# pneuBoard.net
KiCad netlist of a schematic drawn in EAGLE
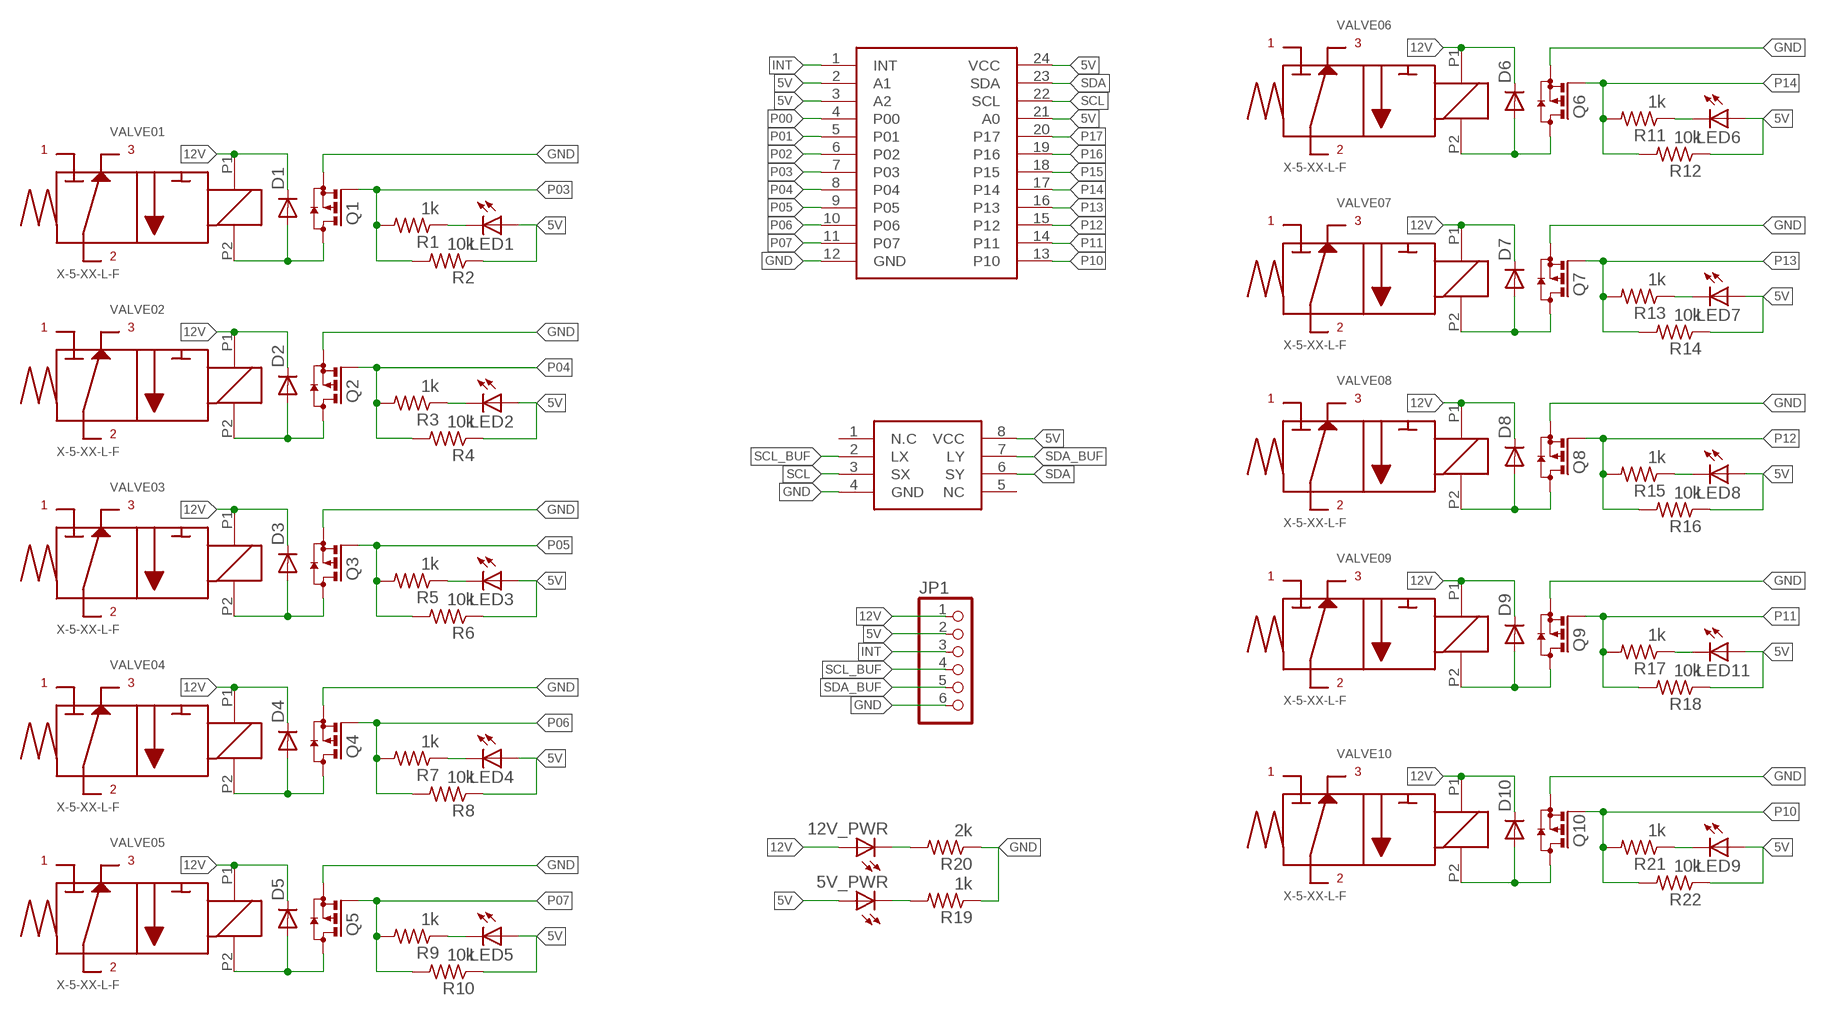
[diagram p0: schematic, sheet 1]

(export (version "E")
  (design (tool "Eeschema 10.0.6"))
  (components
    (comp (ref "5V_PWR")
      (value "LEDSML1206")
      (footprint "eagle-import:SML1206")
      (libsource (lib "eagle-import") (part "LEDSML1206"))
    )
    (comp (ref "12V_PWR")
      (value "LEDSML1206")
      (footprint "eagle-import:SML1206")
      (libsource (lib "eagle-import") (part "LEDSML1206"))
    )
    (comp (ref "D1")
      (value "DIODE-SOD123")
      (footprint "eagle-import:SOD123")
      (libsource (lib "eagle-import") (part "DIODE-SOD123"))
    )
    (comp (ref "D2")
      (value "DIODE-SOD123")
      (footprint "eagle-import:SOD123")
      (libsource (lib "eagle-import") (part "DIODE-SOD123"))
    )
    (comp (ref "D3")
      (value "DIODE-SOD123")
      (footprint "eagle-import:SOD123")
      (libsource (lib "eagle-import") (part "DIODE-SOD123"))
    )
    (comp (ref "D4")
      (value "DIODE-SOD123")
      (footprint "eagle-import:SOD123")
      (libsource (lib "eagle-import") (part "DIODE-SOD123"))
    )
    (comp (ref "D5")
      (value "DIODE-SOD123")
      (footprint "eagle-import:SOD123")
      (libsource (lib "eagle-import") (part "DIODE-SOD123"))
    )
    (comp (ref "D6")
      (value "DIODE-SOD123")
      (footprint "eagle-import:SOD123")
      (libsource (lib "eagle-import") (part "DIODE-SOD123"))
    )
    (comp (ref "D7")
      (value "DIODE-SOD123")
      (footprint "eagle-import:SOD123")
      (libsource (lib "eagle-import") (part "DIODE-SOD123"))
    )
    (comp (ref "D8")
      (value "DIODE-SOD123")
      (footprint "eagle-import:SOD123")
      (libsource (lib "eagle-import") (part "DIODE-SOD123"))
    )
    (comp (ref "D9")
      (value "DIODE-SOD123")
      (footprint "eagle-import:SOD123")
      (libsource (lib "eagle-import") (part "DIODE-SOD123"))
    )
    (comp (ref "D10")
      (value "DIODE-SOD123")
      (footprint "eagle-import:SOD123")
      (libsource (lib "eagle-import") (part "DIODE-SOD123"))
    )
    (comp (ref "JP1")
      (value "PINHD-1X6/90")
      (footprint "eagle-import:1X06_90")
      (libsource (lib "eagle-import") (part "PINHD-1X6/90"))
    )
    (comp (ref "LED1")
      (value "LEDSML1206")
      (footprint "eagle-import:SML1206")
      (libsource (lib "eagle-import") (part "LEDSML1206"))
    )
    (comp (ref "LED2")
      (value "LEDSML1206")
      (footprint "eagle-import:SML1206")
      (libsource (lib "eagle-import") (part "LEDSML1206"))
    )
    (comp (ref "LED3")
      (value "LEDSML1206")
      (footprint "eagle-import:SML1206")
      (libsource (lib "eagle-import") (part "LEDSML1206"))
    )
    (comp (ref "LED4")
      (value "LEDSML1206")
      (footprint "eagle-import:SML1206")
      (libsource (lib "eagle-import") (part "LEDSML1206"))
    )
    (comp (ref "LED5")
      (value "LEDSML1206")
      (footprint "eagle-import:SML1206")
      (libsource (lib "eagle-import") (part "LEDSML1206"))
    )
    (comp (ref "LED6")
      (value "LEDSML1206")
      (footprint "eagle-import:SML1206")
      (libsource (lib "eagle-import") (part "LEDSML1206"))
    )
    (comp (ref "LED7")
      (value "LEDSML1206")
      (footprint "eagle-import:SML1206")
      (libsource (lib "eagle-import") (part "LEDSML1206"))
    )
    (comp (ref "LED8")
      (value "LEDSML1206")
      (footprint "eagle-import:SML1206")
      (libsource (lib "eagle-import") (part "LEDSML1206"))
    )
    (comp (ref "LED9")
      (value "LEDSML1206")
      (footprint "eagle-import:SML1206")
      (libsource (lib "eagle-import") (part "LEDSML1206"))
    )
    (comp (ref "LED11")
      (value "LEDSML1206")
      (footprint "eagle-import:SML1206")
      (libsource (lib "eagle-import") (part "LEDSML1206"))
    )
    (comp (ref "Q1")
      (value "BSS84")
      (footprint "eagle-import:SOT23")
      (libsource (lib "eagle-import") (part "BSS84"))
    )
    (comp (ref "Q2")
      (value "BSS84")
      (footprint "eagle-import:SOT23")
      (libsource (lib "eagle-import") (part "BSS84"))
    )
    (comp (ref "Q3")
      (value "BSS84")
      (footprint "eagle-import:SOT23")
      (libsource (lib "eagle-import") (part "BSS84"))
    )
    (comp (ref "Q4")
      (value "BSS84")
      (footprint "eagle-import:SOT23")
      (libsource (lib "eagle-import") (part "BSS84"))
    )
    (comp (ref "Q5")
      (value "BSS84")
      (footprint "eagle-import:SOT23")
      (libsource (lib "eagle-import") (part "BSS84"))
    )
    (comp (ref "Q6")
      (value "BSS84")
      (footprint "eagle-import:SOT23")
      (libsource (lib "eagle-import") (part "BSS84"))
    )
    (comp (ref "Q7")
      (value "BSS84")
      (footprint "eagle-import:SOT23")
      (libsource (lib "eagle-import") (part "BSS84"))
    )
    (comp (ref "Q8")
      (value "BSS84")
      (footprint "eagle-import:SOT23")
      (libsource (lib "eagle-import") (part "BSS84"))
    )
    (comp (ref "Q9")
      (value "BSS84")
      (footprint "eagle-import:SOT23")
      (libsource (lib "eagle-import") (part "BSS84"))
    )
    (comp (ref "Q10")
      (value "BSS84")
      (footprint "eagle-import:SOT23")
      (libsource (lib "eagle-import") (part "BSS84"))
    )
    (comp (ref "R1")
      (value "1k")
      (footprint "eagle-import:R0603")
      (libsource (lib "eagle-import") (part "R-US_R0603"))
    )
    (comp (ref "R2")
      (value "10k")
      (footprint "eagle-import:R0603")
      (libsource (lib "eagle-import") (part "R-US_R0603"))
    )
    (comp (ref "R3")
      (value "1k")
      (footprint "eagle-import:R0603")
      (libsource (lib "eagle-import") (part "R-US_R0603"))
    )
    (comp (ref "R4")
      (value "10k")
      (footprint "eagle-import:R0603")
      (libsource (lib "eagle-import") (part "R-US_R0603"))
    )
    (comp (ref "R5")
      (value "1k")
      (footprint "eagle-import:R0603")
      (libsource (lib "eagle-import") (part "R-US_R0603"))
    )
    (comp (ref "R6")
      (value "10k")
      (footprint "eagle-import:R0603")
      (libsource (lib "eagle-import") (part "R-US_R0603"))
    )
    (comp (ref "R7")
      (value "1k")
      (footprint "eagle-import:R0603")
      (libsource (lib "eagle-import") (part "R-US_R0603"))
    )
    (comp (ref "R8")
      (value "10k")
      (footprint "eagle-import:R0603")
      (libsource (lib "eagle-import") (part "R-US_R0603"))
    )
    (comp (ref "R9")
      (value "1k")
      (footprint "eagle-import:R0603")
      (libsource (lib "eagle-import") (part "R-US_R0603"))
    )
    (comp (ref "R10")
      (value "10k")
      (footprint "eagle-import:R0603")
      (libsource (lib "eagle-import") (part "R-US_R0603"))
    )
    (comp (ref "R11")
      (value "1k")
      (footprint "eagle-import:R0603")
      (libsource (lib "eagle-import") (part "R-US_R0603"))
    )
    (comp (ref "R12")
      (value "10k")
      (footprint "eagle-import:R0603")
      (libsource (lib "eagle-import") (part "R-US_R0603"))
    )
    (comp (ref "R13")
      (value "1k")
      (footprint "eagle-import:R0603")
      (libsource (lib "eagle-import") (part "R-US_R0603"))
    )
    (comp (ref "R14")
      (value "10k")
      (footprint "eagle-import:R0603")
      (libsource (lib "eagle-import") (part "R-US_R0603"))
    )
    (comp (ref "R15")
      (value "1k")
      (footprint "eagle-import:R0603")
      (libsource (lib "eagle-import") (part "R-US_R0603"))
    )
    (comp (ref "R16")
      (value "10k")
      (footprint "eagle-import:R0603")
      (libsource (lib "eagle-import") (part "R-US_R0603"))
    )
    (comp (ref "R17")
      (value "1k")
      (footprint "eagle-import:R0603")
      (libsource (lib "eagle-import") (part "R-US_R0603"))
    )
    (comp (ref "R18")
      (value "10k")
      (footprint "eagle-import:R0603")
      (libsource (lib "eagle-import") (part "R-US_R0603"))
    )
    (comp (ref "R19")
      (value "1k")
      (footprint "eagle-import:R0603")
      (libsource (lib "eagle-import") (part "R-US_R0603"))
    )
    (comp (ref "R20")
      (value "2k")
      (footprint "eagle-import:R0603")
      (libsource (lib "eagle-import") (part "R-US_R0603"))
    )
    (comp (ref "R21")
      (value "1k")
      (footprint "eagle-import:R0603")
      (libsource (lib "eagle-import") (part "R-US_R0603"))
    )
    (comp (ref "R22")
      (value "10k")
      (footprint "eagle-import:R0603")
      (libsource (lib "eagle-import") (part "R-US_R0603"))
    )
    (comp (ref "U$1")
      (value "PCF8575C")
      (footprint "eagle-import:PW_R-PDSO-G24")
      (libsource (lib "eagle-import") (part "PCF8575C"))
    )
    (comp (ref "U$2")
      (value "P82B715")
      (footprint "eagle-import:SO8")
      (libsource (lib "eagle-import") (part "P82B715"))
    )
    (comp (ref "VALVE01")
      (value "X-5-XX-L-F")
      (footprint "eagle-import:X-SERIES")
      (libsource (lib "eagle-import") (part "X-5-XX-L-F"))
    )
    (comp (ref "VALVE02")
      (value "X-5-XX-L-F")
      (footprint "eagle-import:X-SERIES")
      (libsource (lib "eagle-import") (part "X-5-XX-L-F"))
    )
    (comp (ref "VALVE03")
      (value "X-5-XX-L-F")
      (footprint "eagle-import:X-SERIES")
      (libsource (lib "eagle-import") (part "X-5-XX-L-F"))
    )
    (comp (ref "VALVE04")
      (value "X-5-XX-L-F")
      (footprint "eagle-import:X-SERIES")
      (libsource (lib "eagle-import") (part "X-5-XX-L-F"))
    )
    (comp (ref "VALVE05")
      (value "X-5-XX-L-F")
      (footprint "eagle-import:X-SERIES")
      (libsource (lib "eagle-import") (part "X-5-XX-L-F"))
    )
    (comp (ref "VALVE06")
      (value "X-5-XX-L-F")
      (footprint "eagle-import:X-SERIES")
      (libsource (lib "eagle-import") (part "X-5-XX-L-F"))
    )
    (comp (ref "VALVE07")
      (value "X-5-XX-L-F")
      (footprint "eagle-import:X-SERIES")
      (libsource (lib "eagle-import") (part "X-5-XX-L-F"))
    )
    (comp (ref "VALVE08")
      (value "X-5-XX-L-F")
      (footprint "eagle-import:X-SERIES")
      (libsource (lib "eagle-import") (part "X-5-XX-L-F"))
    )
    (comp (ref "VALVE09")
      (value "X-5-XX-L-F")
      (footprint "eagle-import:X-SERIES")
      (libsource (lib "eagle-import") (part "X-5-XX-L-F"))
    )
    (comp (ref "VALVE10")
      (value "X-5-XX-L-F")
      (footprint "eagle-import:X-SERIES")
      (libsource (lib "eagle-import") (part "X-5-XX-L-F"))
    )
  )
  (nets
    (net (code "1") (name "5V") (class "Default")
      (node (ref "5V_PWR") (pin "A") (pinfunction "A_A") (pintype "passive"))
      (node (ref "JP1") (pin "2") (pinfunction "2_2") (pintype "passive"))
      (node (ref "LED1") (pin "A") (pinfunction "A_A") (pintype "passive"))
      (node (ref "LED11") (pin "A") (pinfunction "A_A") (pintype "passive"))
      (node (ref "LED2") (pin "A") (pinfunction "A_A") (pintype "passive"))
      (node (ref "LED3") (pin "A") (pinfunction "A_A") (pintype "passive"))
      (node (ref "LED4") (pin "A") (pinfunction "A_A") (pintype "passive"))
      (node (ref "LED5") (pin "A") (pinfunction "A_A") (pintype "passive"))
      (node (ref "LED6") (pin "A") (pinfunction "A_A") (pintype "passive"))
      (node (ref "LED7") (pin "A") (pinfunction "A_A") (pintype "passive"))
      (node (ref "LED8") (pin "A") (pinfunction "A_A") (pintype "passive"))
      (node (ref "LED9") (pin "A") (pinfunction "A_A") (pintype "passive"))
      (node (ref "R10") (pin "1") (pinfunction "1_1") (pintype "passive"))
      (node (ref "R12") (pin "1") (pinfunction "1_1") (pintype "passive"))
      (node (ref "R14") (pin "1") (pinfunction "1_1") (pintype "passive"))
      (node (ref "R16") (pin "1") (pinfunction "1_1") (pintype "passive"))
      (node (ref "R18") (pin "1") (pinfunction "1_1") (pintype "passive"))
      (node (ref "R2") (pin "1") (pinfunction "1_1") (pintype "passive"))
      (node (ref "R22") (pin "1") (pinfunction "1_1") (pintype "passive"))
      (node (ref "R4") (pin "1") (pinfunction "1_1") (pintype "passive"))
      (node (ref "R6") (pin "1") (pinfunction "1_1") (pintype "passive"))
      (node (ref "R8") (pin "1") (pinfunction "1_1") (pintype "passive"))
      (node (ref "U$1") (pin "2") (pinfunction "A1_2") (pintype "bidirectional"))
      (node (ref "U$1") (pin "21") (pinfunction "A0_21") (pintype "bidirectional"))
      (node (ref "U$1") (pin "24") (pinfunction "VCC_24") (pintype "bidirectional"))
      (node (ref "U$1") (pin "3") (pinfunction "A2_3") (pintype "bidirectional"))
      (node (ref "U$2") (pin "8") (pinfunction "VCC_8") (pintype "bidirectional"))
    )
    (net (code "2") (name "12V") (class "Default")
      (node (ref "12V_PWR") (pin "A") (pinfunction "A_A") (pintype "passive"))
      (node (ref "D1") (pin "C") (pinfunction "C_C") (pintype "passive"))
      (node (ref "D10") (pin "C") (pinfunction "C_C") (pintype "passive"))
      (node (ref "D2") (pin "C") (pinfunction "C_C") (pintype "passive"))
      (node (ref "D3") (pin "C") (pinfunction "C_C") (pintype "passive"))
      (node (ref "D4") (pin "C") (pinfunction "C_C") (pintype "passive"))
      (node (ref "D5") (pin "C") (pinfunction "C_C") (pintype "passive"))
      (node (ref "D6") (pin "C") (pinfunction "C_C") (pintype "passive"))
      (node (ref "D7") (pin "C") (pinfunction "C_C") (pintype "passive"))
      (node (ref "D8") (pin "C") (pinfunction "C_C") (pintype "passive"))
      (node (ref "D9") (pin "C") (pinfunction "C_C") (pintype "passive"))
      (node (ref "JP1") (pin "1") (pinfunction "1_1") (pintype "passive"))
      (node (ref "VALVE01") (pin "P1") (pinfunction "1_P1") (pintype "bidirectional"))
      (node (ref "VALVE02") (pin "P1") (pinfunction "1_P1") (pintype "bidirectional"))
      (node (ref "VALVE03") (pin "P1") (pinfunction "1_P1") (pintype "bidirectional"))
      (node (ref "VALVE04") (pin "P1") (pinfunction "1_P1") (pintype "bidirectional"))
      (node (ref "VALVE05") (pin "P1") (pinfunction "1_P1") (pintype "bidirectional"))
      (node (ref "VALVE06") (pin "P1") (pinfunction "1_P1") (pintype "bidirectional"))
      (node (ref "VALVE07") (pin "P1") (pinfunction "1_P1") (pintype "bidirectional"))
      (node (ref "VALVE08") (pin "P1") (pinfunction "1_P1") (pintype "bidirectional"))
      (node (ref "VALVE09") (pin "P1") (pinfunction "1_P1") (pintype "bidirectional"))
      (node (ref "VALVE10") (pin "P1") (pinfunction "1_P1") (pintype "bidirectional"))
    )
    (net (code "3") (name "GND") (class "Default")
      (node (ref "JP1") (pin "6") (pinfunction "6_6") (pintype "passive"))
      (node (ref "Q1") (pin "2") (pinfunction "S_2") (pintype "passive"))
      (node (ref "Q10") (pin "2") (pinfunction "S_2") (pintype "passive"))
      (node (ref "Q2") (pin "2") (pinfunction "S_2") (pintype "passive"))
      (node (ref "Q3") (pin "2") (pinfunction "S_2") (pintype "passive"))
      (node (ref "Q4") (pin "2") (pinfunction "S_2") (pintype "passive"))
      (node (ref "Q5") (pin "2") (pinfunction "S_2") (pintype "passive"))
      (node (ref "Q6") (pin "2") (pinfunction "S_2") (pintype "passive"))
      (node (ref "Q7") (pin "2") (pinfunction "S_2") (pintype "passive"))
      (node (ref "Q8") (pin "2") (pinfunction "S_2") (pintype "passive"))
      (node (ref "Q9") (pin "2") (pinfunction "S_2") (pintype "passive"))
      (node (ref "R19") (pin "1") (pinfunction "1_1") (pintype "passive"))
      (node (ref "R20") (pin "1") (pinfunction "1_1") (pintype "passive"))
      (node (ref "U$1") (pin "12") (pinfunction "GND_12") (pintype "bidirectional"))
      (node (ref "U$2") (pin "4") (pinfunction "GND_4") (pintype "bidirectional"))
    )
    (net (code "4") (name "INT") (class "Default")
      (node (ref "JP1") (pin "3") (pinfunction "3_3") (pintype "passive"))
      (node (ref "U$1") (pin "1") (pinfunction "INT_1") (pintype "bidirectional"))
    )
    (net (code "5") (name "Net-(5V_PWR-PadC)") (class "Default")
      (node (ref "5V_PWR") (pin "C") (pinfunction "C_C") (pintype "passive"))
      (node (ref "R19") (pin "2") (pinfunction "2_2") (pintype "passive"))
    )
    (net (code "6") (name "Net-(12V_PWR-PadC)") (class "Default")
      (node (ref "12V_PWR") (pin "C") (pinfunction "C_C") (pintype "passive"))
      (node (ref "R20") (pin "2") (pinfunction "2_2") (pintype "passive"))
    )
    (net (code "7") (name "Net-(LED1-PadC)") (class "Default")
      (node (ref "LED1") (pin "C") (pinfunction "C_C") (pintype "passive"))
      (node (ref "R1") (pin "1") (pinfunction "1_1") (pintype "passive"))
    )
    (net (code "8") (name "Net-(LED2-PadC)") (class "Default")
      (node (ref "LED2") (pin "C") (pinfunction "C_C") (pintype "passive"))
      (node (ref "R3") (pin "1") (pinfunction "1_1") (pintype "passive"))
    )
    (net (code "9") (name "Net-(LED3-PadC)") (class "Default")
      (node (ref "LED3") (pin "C") (pinfunction "C_C") (pintype "passive"))
      (node (ref "R5") (pin "1") (pinfunction "1_1") (pintype "passive"))
    )
    (net (code "10") (name "Net-(LED4-PadC)") (class "Default")
      (node (ref "LED4") (pin "C") (pinfunction "C_C") (pintype "passive"))
      (node (ref "R7") (pin "1") (pinfunction "1_1") (pintype "passive"))
    )
    (net (code "11") (name "Net-(LED5-PadC)") (class "Default")
      (node (ref "LED5") (pin "C") (pinfunction "C_C") (pintype "passive"))
      (node (ref "R9") (pin "1") (pinfunction "1_1") (pintype "passive"))
    )
    (net (code "12") (name "Net-(LED6-PadC)") (class "Default")
      (node (ref "LED6") (pin "C") (pinfunction "C_C") (pintype "passive"))
      (node (ref "R11") (pin "1") (pinfunction "1_1") (pintype "passive"))
    )
    (net (code "13") (name "Net-(LED7-PadC)") (class "Default")
      (node (ref "LED7") (pin "C") (pinfunction "C_C") (pintype "passive"))
      (node (ref "R13") (pin "1") (pinfunction "1_1") (pintype "passive"))
    )
    (net (code "14") (name "Net-(LED8-PadC)") (class "Default")
      (node (ref "LED8") (pin "C") (pinfunction "C_C") (pintype "passive"))
      (node (ref "R15") (pin "1") (pinfunction "1_1") (pintype "passive"))
    )
    (net (code "15") (name "Net-(LED9-PadC)") (class "Default")
      (node (ref "LED9") (pin "C") (pinfunction "C_C") (pintype "passive"))
      (node (ref "R21") (pin "1") (pinfunction "1_1") (pintype "passive"))
    )
    (net (code "16") (name "Net-(LED11-PadC)") (class "Default")
      (node (ref "LED11") (pin "C") (pinfunction "C_C") (pintype "passive"))
      (node (ref "R17") (pin "1") (pinfunction "1_1") (pintype "passive"))
    )
    (net (code "17") (name "Net-(Q1-D)") (class "Default")
      (node (ref "D1") (pin "A") (pinfunction "A_A") (pintype "passive"))
      (node (ref "Q1") (pin "3") (pinfunction "D_3") (pintype "passive"))
      (node (ref "VALVE01") (pin "P2") (pinfunction "2_P2") (pintype "bidirectional"))
    )
    (net (code "18") (name "Net-(Q2-D)") (class "Default")
      (node (ref "D2") (pin "A") (pinfunction "A_A") (pintype "passive"))
      (node (ref "Q2") (pin "3") (pinfunction "D_3") (pintype "passive"))
      (node (ref "VALVE02") (pin "P2") (pinfunction "2_P2") (pintype "bidirectional"))
    )
    (net (code "19") (name "Net-(Q3-D)") (class "Default")
      (node (ref "D3") (pin "A") (pinfunction "A_A") (pintype "passive"))
      (node (ref "Q3") (pin "3") (pinfunction "D_3") (pintype "passive"))
      (node (ref "VALVE03") (pin "P2") (pinfunction "2_P2") (pintype "bidirectional"))
    )
    (net (code "20") (name "Net-(Q4-D)") (class "Default")
      (node (ref "D4") (pin "A") (pinfunction "A_A") (pintype "passive"))
      (node (ref "Q4") (pin "3") (pinfunction "D_3") (pintype "passive"))
      (node (ref "VALVE04") (pin "P2") (pinfunction "2_P2") (pintype "bidirectional"))
    )
    (net (code "21") (name "Net-(Q5-D)") (class "Default")
      (node (ref "D5") (pin "A") (pinfunction "A_A") (pintype "passive"))
      (node (ref "Q5") (pin "3") (pinfunction "D_3") (pintype "passive"))
      (node (ref "VALVE05") (pin "P2") (pinfunction "2_P2") (pintype "bidirectional"))
    )
    (net (code "22") (name "Net-(Q6-D)") (class "Default")
      (node (ref "D6") (pin "A") (pinfunction "A_A") (pintype "passive"))
      (node (ref "Q6") (pin "3") (pinfunction "D_3") (pintype "passive"))
      (node (ref "VALVE06") (pin "P2") (pinfunction "2_P2") (pintype "bidirectional"))
    )
    (net (code "23") (name "Net-(Q7-D)") (class "Default")
      (node (ref "D7") (pin "A") (pinfunction "A_A") (pintype "passive"))
      (node (ref "Q7") (pin "3") (pinfunction "D_3") (pintype "passive"))
      (node (ref "VALVE07") (pin "P2") (pinfunction "2_P2") (pintype "bidirectional"))
    )
    (net (code "24") (name "Net-(Q8-D)") (class "Default")
      (node (ref "D8") (pin "A") (pinfunction "A_A") (pintype "passive"))
      (node (ref "Q8") (pin "3") (pinfunction "D_3") (pintype "passive"))
      (node (ref "VALVE08") (pin "P2") (pinfunction "2_P2") (pintype "bidirectional"))
    )
    (net (code "25") (name "Net-(Q9-D)") (class "Default")
      (node (ref "D9") (pin "A") (pinfunction "A_A") (pintype "passive"))
      (node (ref "Q9") (pin "3") (pinfunction "D_3") (pintype "passive"))
      (node (ref "VALVE09") (pin "P2") (pinfunction "2_P2") (pintype "bidirectional"))
    )
    (net (code "26") (name "Net-(Q10-D)") (class "Default")
      (node (ref "D10") (pin "A") (pinfunction "A_A") (pintype "passive"))
      (node (ref "Q10") (pin "3") (pinfunction "D_3") (pintype "passive"))
      (node (ref "VALVE10") (pin "P2") (pinfunction "2_P2") (pintype "bidirectional"))
    )
    (net (code "27") (name "P00") (class "Default")
      (node (ref "U$1") (pin "4") (pinfunction "P00_4") (pintype "bidirectional"))
    )
    (net (code "28") (name "P01") (class "Default")
      (node (ref "U$1") (pin "5") (pinfunction "P01_5") (pintype "bidirectional"))
    )
    (net (code "29") (name "P02") (class "Default")
      (node (ref "U$1") (pin "6") (pinfunction "P02_6") (pintype "bidirectional"))
    )
    (net (code "30") (name "P03") (class "Default")
      (node (ref "Q1") (pin "1") (pinfunction "G_1") (pintype "passive"))
      (node (ref "R1") (pin "2") (pinfunction "2_2") (pintype "passive"))
      (node (ref "R2") (pin "2") (pinfunction "2_2") (pintype "passive"))
      (node (ref "U$1") (pin "7") (pinfunction "P03_7") (pintype "bidirectional"))
    )
    (net (code "31") (name "P04") (class "Default")
      (node (ref "Q2") (pin "1") (pinfunction "G_1") (pintype "passive"))
      (node (ref "R3") (pin "2") (pinfunction "2_2") (pintype "passive"))
      (node (ref "R4") (pin "2") (pinfunction "2_2") (pintype "passive"))
      (node (ref "U$1") (pin "8") (pinfunction "P04_8") (pintype "bidirectional"))
    )
    (net (code "32") (name "P05") (class "Default")
      (node (ref "Q3") (pin "1") (pinfunction "G_1") (pintype "passive"))
      (node (ref "R5") (pin "2") (pinfunction "2_2") (pintype "passive"))
      (node (ref "R6") (pin "2") (pinfunction "2_2") (pintype "passive"))
      (node (ref "U$1") (pin "9") (pinfunction "P05_9") (pintype "bidirectional"))
    )
    (net (code "33") (name "P06") (class "Default")
      (node (ref "Q4") (pin "1") (pinfunction "G_1") (pintype "passive"))
      (node (ref "R7") (pin "2") (pinfunction "2_2") (pintype "passive"))
      (node (ref "R8") (pin "2") (pinfunction "2_2") (pintype "passive"))
      (node (ref "U$1") (pin "10") (pinfunction "P06_10") (pintype "bidirectional"))
    )
    (net (code "34") (name "P07") (class "Default")
      (node (ref "Q5") (pin "1") (pinfunction "G_1") (pintype "passive"))
      (node (ref "R10") (pin "2") (pinfunction "2_2") (pintype "passive"))
      (node (ref "R9") (pin "2") (pinfunction "2_2") (pintype "passive"))
      (node (ref "U$1") (pin "11") (pinfunction "P07_11") (pintype "bidirectional"))
    )
    (net (code "35") (name "P10") (class "Default")
      (node (ref "Q10") (pin "1") (pinfunction "G_1") (pintype "passive"))
      (node (ref "R21") (pin "2") (pinfunction "2_2") (pintype "passive"))
      (node (ref "R22") (pin "2") (pinfunction "2_2") (pintype "passive"))
      (node (ref "U$1") (pin "13") (pinfunction "P10_13") (pintype "bidirectional"))
    )
    (net (code "36") (name "P11") (class "Default")
      (node (ref "Q9") (pin "1") (pinfunction "G_1") (pintype "passive"))
      (node (ref "R17") (pin "2") (pinfunction "2_2") (pintype "passive"))
      (node (ref "R18") (pin "2") (pinfunction "2_2") (pintype "passive"))
      (node (ref "U$1") (pin "14") (pinfunction "P11_14") (pintype "bidirectional"))
    )
    (net (code "37") (name "P12") (class "Default")
      (node (ref "Q8") (pin "1") (pinfunction "G_1") (pintype "passive"))
      (node (ref "R15") (pin "2") (pinfunction "2_2") (pintype "passive"))
      (node (ref "R16") (pin "2") (pinfunction "2_2") (pintype "passive"))
      (node (ref "U$1") (pin "15") (pinfunction "P12_15") (pintype "bidirectional"))
    )
    (net (code "38") (name "P13") (class "Default")
      (node (ref "Q7") (pin "1") (pinfunction "G_1") (pintype "passive"))
      (node (ref "R13") (pin "2") (pinfunction "2_2") (pintype "passive"))
      (node (ref "R14") (pin "2") (pinfunction "2_2") (pintype "passive"))
      (node (ref "U$1") (pin "16") (pinfunction "P13_16") (pintype "bidirectional"))
    )
    (net (code "39") (name "P14") (class "Default")
      (node (ref "Q6") (pin "1") (pinfunction "G_1") (pintype "passive"))
      (node (ref "R11") (pin "2") (pinfunction "2_2") (pintype "passive"))
      (node (ref "R12") (pin "2") (pinfunction "2_2") (pintype "passive"))
      (node (ref "U$1") (pin "17") (pinfunction "P14_17") (pintype "bidirectional"))
    )
    (net (code "40") (name "P15") (class "Default")
      (node (ref "U$1") (pin "18") (pinfunction "P15_18") (pintype "bidirectional"))
    )
    (net (code "41") (name "P16") (class "Default")
      (node (ref "U$1") (pin "19") (pinfunction "P16_19") (pintype "bidirectional"))
    )
    (net (code "42") (name "P17") (class "Default")
      (node (ref "U$1") (pin "20") (pinfunction "P17_20") (pintype "bidirectional"))
    )
    (net (code "43") (name "SCL") (class "Default")
      (node (ref "U$1") (pin "22") (pinfunction "SCL_22") (pintype "bidirectional"))
      (node (ref "U$2") (pin "3") (pinfunction "SX_3") (pintype "bidirectional"))
    )
    (net (code "44") (name "SCL_BUF") (class "Default")
      (node (ref "JP1") (pin "4") (pinfunction "4_4") (pintype "passive"))
      (node (ref "U$2") (pin "2") (pinfunction "LX_2") (pintype "bidirectional"))
    )
    (net (code "45") (name "SDA") (class "Default")
      (node (ref "U$1") (pin "23") (pinfunction "SDA_23") (pintype "bidirectional"))
      (node (ref "U$2") (pin "6") (pinfunction "SY_6") (pintype "bidirectional"))
    )
    (net (code "46") (name "SDA_BUF") (class "Default")
      (node (ref "JP1") (pin "5") (pinfunction "5_5") (pintype "passive"))
      (node (ref "U$2") (pin "7") (pinfunction "LY_7") (pintype "bidirectional"))
    )
    (net (code "47") (name "unconnected-(U$2-N.C-Pad1)") (class "Default")
      (node (ref "U$2") (pin "1") (pinfunction "N.C_1") (pintype "bidirectional"))
    )
    (net (code "48") (name "unconnected-(U$2-NC-Pad5)") (class "Default")
      (node (ref "U$2") (pin "5") (pinfunction "NC_5") (pintype "bidirectional"))
    )
  )
)
